# MCU.net
KiCad netlist of a schematic drawn in Altium Designer
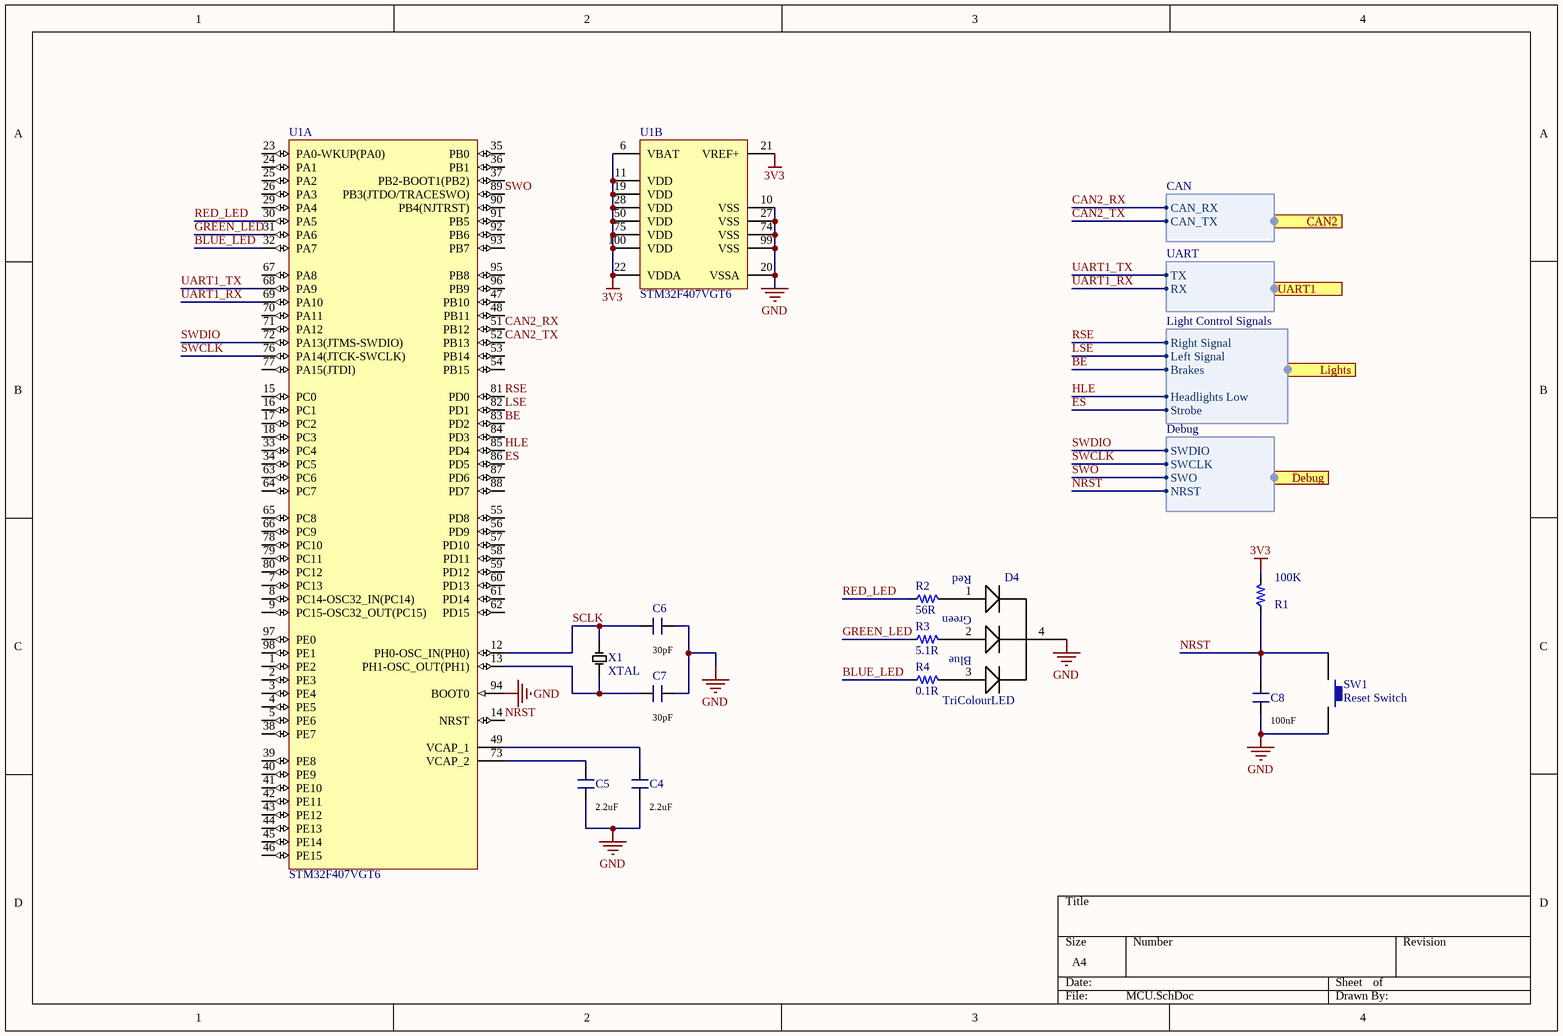
[diagram p0: MCU.SchDoc]

(export (version "E")
  (design (tool "Eeschema 10.0.6"))
  (components
    (comp (ref "C4")
      (value "SCH_GENERIC_CAPACITOR_0603")
      (footprint "PCB_GENERIC_SMD_0603")
      (description "Generic SMD capacitor 0603")
      (fields (field (name "TOLERANCE") "*%") (field (name "CAPACITANCE") "2.2uF"))
      (libsource (lib "Capacitors") (part "SCH_GENERIC_CAPACITOR_0603"))
    )
    (comp (ref "C5")
      (value "SCH_GENERIC_CAPACITOR_0603")
      (footprint "PCB_GENERIC_SMD_0603")
      (description "Generic SMD capacitor 0603")
      (fields (field (name "TOLERANCE") "*%") (field (name "CAPACITANCE") "2.2uF"))
      (libsource (lib "Capacitors") (part "SCH_GENERIC_CAPACITOR_0603"))
    )
    (comp (ref "C6")
      (value "SCH_GENERIC_CAPACITOR_0603")
      (footprint "PCB_GENERIC_SMD_0603")
      (description "Generic SMD capacitor 0603")
      (fields (field (name "TOLERANCE") "*%") (field (name "CAPACITANCE") "30pF"))
      (libsource (lib "Capacitors") (part "SCH_GENERIC_CAPACITOR_0603"))
    )
    (comp (ref "C7")
      (value "SCH_GENERIC_CAPACITOR_0603")
      (footprint "PCB_GENERIC_SMD_0603")
      (description "Generic SMD capacitor 0603")
      (fields (field (name "TOLERANCE") "*%") (field (name "CAPACITANCE") "30pF"))
      (libsource (lib "Capacitors") (part "SCH_GENERIC_CAPACITOR_0603"))
    )
    (comp (ref "C8")
      (value "SCH_GENERIC_CAPACITOR_0603")
      (footprint "PCB_GENERIC_SMD_0603")
      (description "Generic SMD capacitor 0603")
      (fields (field (name "TOLERANCE") "*%") (field (name "CAPACITANCE") "100nF"))
      (libsource (lib "Capacitors") (part "SCH_GENERIC_CAPACITOR_0603"))
    )
    (comp (ref "D4")
      (value "TriColourLED")
      (footprint "TricolourLED - SunLED - DK  1497-1225-2-ND")
      (libsource (lib "TricolourLED - SunLED - DK 1497-1225-2-ND") (part "TriColourLED"))
    )
    (comp (ref "R1")
      (value "SCH_GENERIC_RESISTOR_0603")
      (footprint "Generic 0603 Resistor:PCB_GENERIC_SMD_0603")
      (description "Generic SMD resistor 0603")
      (fields (field (name "RESISTANCE") "100K"))
      (libsource (lib "Resistors") (part "SCH_GENERIC_RESISTOR_0603"))
    )
    (comp (ref "R2")
      (value "SCH_GENERIC_RESISTOR_0603")
      (footprint "Generic 0603 Resistor:PCB_GENERIC_SMD_0603")
      (description "Generic SMD resistor 0603")
      (fields (field (name "RESISTANCE") "56R"))
      (libsource (lib "SCH_GENERIC_RESISTOR_0603") (part "SCH_GENERIC_RESISTOR_0603"))
    )
    (comp (ref "R3")
      (value "SCH_GENERIC_RESISTOR_0603")
      (footprint "Generic 0603 Resistor:PCB_GENERIC_SMD_0603")
      (description "Generic SMD resistor 0603")
      (fields (field (name "RESISTANCE") "5.1R"))
      (libsource (lib "SCH_GENERIC_RESISTOR_0603") (part "SCH_GENERIC_RESISTOR_0603"))
    )
    (comp (ref "R4")
      (value "SCH_GENERIC_RESISTOR_0603")
      (footprint "Generic 0603 Resistor:PCB_GENERIC_SMD_0603")
      (description "Generic SMD resistor 0603")
      (fields (field (name "RESISTANCE") "0.1R"))
      (libsource (lib "SCH_GENERIC_RESISTOR_0603") (part "SCH_GENERIC_RESISTOR_0603"))
    )
    (comp (ref "SW1")
      (value "Reset Switch")
      (footprint "Push Button Switch")
      (libsource (lib "PushButtonSwitch") (part "PushButtonSwitch"))
    )
    (comp (ref "U1")
      (value "STM32F407VGT6")
      (footprint "STM-LQFP100_N")
      (fields (field (name "MANUFACTURER") "STMicroelectronics"))
      (libsource (lib "STMicroelectronics STM32 F4") (part "STM32F407VGT6"))
    )
    (comp (ref "X1") (value "XTAL") (footprint "CRYSTAL_8MHZ") (libsource (lib "Crystal") (part "Crystal")))
  )
  (nets
    (net (code "7") (name "/BE") (class "Default")
      (node (ref "U1") (pin "83") (pinfunction "PD2_83") (pintype "bidirectional"))
    )
    (net (code "8") (name "/BLUE_LED") (class "Default")
      (node (ref "R4") (pin "1") (pinfunction "1_1") (pintype "passive"))
      (node (ref "U1") (pin "32") (pinfunction "PA7_32") (pintype "bidirectional"))
    )
    (net (code "9") (name "/CAN2_RX") (class "Default")
      (node (ref "U1") (pin "51") (pinfunction "PB12_51") (pintype "bidirectional"))
    )
    (net (code "10") (name "/CAN2_TX") (class "Default")
      (node (ref "U1") (pin "52") (pinfunction "PB13_52") (pintype "bidirectional"))
    )
    (net (code "11") (name "/ES") (class "Default")
      (node (ref "U1") (pin "86") (pinfunction "PD5_86") (pintype "bidirectional"))
    )
    (net (code "12") (name "/GREEN_LED") (class "Default")
      (node (ref "R3") (pin "1") (pinfunction "1_1") (pintype "passive"))
      (node (ref "U1") (pin "31") (pinfunction "PA6_31") (pintype "bidirectional"))
    )
    (net (code "13") (name "/HLE") (class "Default")
      (node (ref "U1") (pin "85") (pinfunction "PD4_85") (pintype "bidirectional"))
    )
    (net (code "14") (name "/LSE") (class "Default")
      (node (ref "U1") (pin "82") (pinfunction "PD1_82") (pintype "bidirectional"))
    )
    (net (code "15") (name "/NRST") (class "Default")
      (node (ref "C8") (pin "1") (pinfunction "1_1") (pintype "passive"))
      (node (ref "R1") (pin "1") (pinfunction "1_1") (pintype "passive"))
      (node (ref "SW1") (pin "1") (pinfunction "1_1") (pintype "passive"))
      (node (ref "U1") (pin "14") (pinfunction "NRST_14") (pintype "bidirectional"))
    )
    (net (code "16") (name "/RED_LED") (class "Default")
      (node (ref "R2") (pin "1") (pinfunction "1_1") (pintype "passive"))
      (node (ref "U1") (pin "30") (pinfunction "PA5_30") (pintype "bidirectional"))
    )
    (net (code "17") (name "/RSE") (class "Default")
      (node (ref "U1") (pin "81") (pinfunction "PD0_81") (pintype "bidirectional"))
    )
    (net (code "18") (name "/SCLK") (class "Default")
      (node (ref "C6") (pin "2") (pinfunction "2_2") (pintype "passive"))
      (node (ref "U1") (pin "12") (pinfunction "PH0-OSC_IN(PH0)_12") (pintype "bidirectional"))
      (node (ref "X1") (pin "1") (pintype "passive"))
    )
    (net (code "19") (name "/SWCLK") (class "Default")
      (node (ref "U1") (pin "76") (pinfunction "PA14(JTCK-SWCLK)_76") (pintype "bidirectional"))
    )
    (net (code "20") (name "/SWDIO") (class "Default")
      (node (ref "U1") (pin "72") (pinfunction "PA13(JTMS-SWDIO)_72") (pintype "bidirectional"))
    )
    (net (code "21") (name "/SWO") (class "Default")
      (node (ref "U1") (pin "89") (pinfunction "PB3(JTDO/TRACESWO)_89") (pintype "bidirectional"))
    )
    (net (code "22") (name "/UART1_RX") (class "Default")
      (node (ref "U1") (pin "69") (pinfunction "PA10_69") (pintype "bidirectional"))
    )
    (net (code "23") (name "/UART1_TX") (class "Default")
      (node (ref "U1") (pin "68") (pinfunction "PA9_68") (pintype "bidirectional"))
    )
    (net (code "28") (name "3V3") (class "Default")
      (node (ref "R1") (pin "2") (pinfunction "2_2") (pintype "passive"))
      (node (ref "U1") (pin "100") (pinfunction "VDD_100") (pintype "power_in"))
      (node (ref "U1") (pin "11") (pinfunction "VDD_11") (pintype "power_in"))
      (node (ref "U1") (pin "19") (pinfunction "VDD_19") (pintype "power_in"))
      (node (ref "U1") (pin "21") (pinfunction "VREF+_21") (pintype "power_in"))
      (node (ref "U1") (pin "22") (pinfunction "VDDA_22") (pintype "power_in"))
      (node (ref "U1") (pin "28") (pinfunction "VDD_28") (pintype "power_in"))
      (node (ref "U1") (pin "50") (pinfunction "VDD_50") (pintype "power_in"))
      (node (ref "U1") (pin "6") (pinfunction "VBAT_6") (pintype "power_in"))
      (node (ref "U1") (pin "75") (pinfunction "VDD_75") (pintype "power_in"))
    )
    (net (code "29") (name "GND") (class "Default")
      (node (ref "C4") (pin "1") (pinfunction "1_1") (pintype "passive"))
      (node (ref "C5") (pin "1") (pinfunction "1_1") (pintype "passive"))
      (node (ref "C6") (pin "1") (pinfunction "1_1") (pintype "passive"))
      (node (ref "C7") (pin "1") (pinfunction "1_1") (pintype "passive"))
      (node (ref "C8") (pin "2") (pinfunction "2_2") (pintype "passive"))
      (node (ref "D4") (pin "4") (pinfunction "4_4") (pintype "passive"))
      (node (ref "SW1") (pin "2") (pinfunction "2_2") (pintype "passive"))
      (node (ref "U1") (pin "10") (pinfunction "VSS_10") (pintype "power_in"))
      (node (ref "U1") (pin "20") (pinfunction "VSSA_20") (pintype "power_in"))
      (node (ref "U1") (pin "27") (pinfunction "VSS_27") (pintype "power_in"))
      (node (ref "U1") (pin "74") (pinfunction "VSS_74") (pintype "power_in"))
      (node (ref "U1") (pin "94") (pinfunction "BOOT0_94") (pintype "input"))
      (node (ref "U1") (pin "99") (pinfunction "VSS_99") (pintype "power_in"))
    )
    (net (code "30") (name "Net-(D4-Blue)") (class "Default")
      (node (ref "D4") (pin "3") (pinfunction "Blue_3") (pintype "passive"))
      (node (ref "R4") (pin "2") (pinfunction "2_2") (pintype "passive"))
    )
    (net (code "31") (name "Net-(D4-Green)") (class "Default")
      (node (ref "D4") (pin "2") (pinfunction "Green_2") (pintype "passive"))
      (node (ref "R3") (pin "2") (pinfunction "2_2") (pintype "passive"))
    )
    (net (code "32") (name "Net-(D4-Red)") (class "Default")
      (node (ref "D4") (pin "1") (pinfunction "Red_1") (pintype "passive"))
      (node (ref "R2") (pin "2") (pinfunction "2_2") (pintype "passive"))
    )
    (net (code "33") (name "Net-(U1A-PH1-OSC_OUT(PH1))") (class "Default")
      (node (ref "C7") (pin "2") (pinfunction "2_2") (pintype "passive"))
      (node (ref "U1") (pin "13") (pinfunction "PH1-OSC_OUT(PH1)_13") (pintype "bidirectional"))
      (node (ref "X1") (pin "2") (pintype "passive"))
    )
    (net (code "34") (name "Net-(U1A-VCAP_1)") (class "Default")
      (node (ref "C4") (pin "2") (pinfunction "2_2") (pintype "passive"))
      (node (ref "U1") (pin "49") (pinfunction "VCAP_1_49") (pintype "power_in"))
    )
    (net (code "35") (name "Net-(U1A-VCAP_2)") (class "Default")
      (node (ref "C5") (pin "2") (pinfunction "2_2") (pintype "passive"))
      (node (ref "U1") (pin "73") (pinfunction "VCAP_2_73") (pintype "power_in"))
    )
    (net (code "36") (name "unconnected-(U1A-PA0-WKUP(PA0)-Pad23)") (class "Default")
      (node (ref "U1") (pin "23") (pinfunction "PA0-WKUP(PA0)_23") (pintype "bidirectional"))
    )
    (net (code "37") (name "unconnected-(U1A-PA1-Pad24)") (class "Default")
      (node (ref "U1") (pin "24") (pinfunction "PA1_24") (pintype "bidirectional"))
    )
    (net (code "38") (name "unconnected-(U1A-PA2-Pad25)") (class "Default")
      (node (ref "U1") (pin "25") (pinfunction "PA2_25") (pintype "bidirectional"))
    )
    (net (code "39") (name "unconnected-(U1A-PA3-Pad26)") (class "Default")
      (node (ref "U1") (pin "26") (pinfunction "PA3_26") (pintype "bidirectional"))
    )
    (net (code "40") (name "unconnected-(U1A-PA4-Pad29)") (class "Default")
      (node (ref "U1") (pin "29") (pinfunction "PA4_29") (pintype "bidirectional"))
    )
    (net (code "41") (name "unconnected-(U1A-PA8-Pad67)") (class "Default")
      (node (ref "U1") (pin "67") (pinfunction "PA8_67") (pintype "bidirectional"))
    )
    (net (code "42") (name "unconnected-(U1A-PA11-Pad70)") (class "Default")
      (node (ref "U1") (pin "70") (pinfunction "PA11_70") (pintype "bidirectional"))
    )
    (net (code "43") (name "unconnected-(U1A-PA12-Pad71)") (class "Default")
      (node (ref "U1") (pin "71") (pinfunction "PA12_71") (pintype "bidirectional"))
    )
    (net (code "44") (name "unconnected-(U1A-PA15(JTDI)-Pad77)") (class "Default")
      (node (ref "U1") (pin "77") (pinfunction "PA15(JTDI)_77") (pintype "bidirectional"))
    )
    (net (code "45") (name "unconnected-(U1A-PB0-Pad35)") (class "Default")
      (node (ref "U1") (pin "35") (pinfunction "PB0_35") (pintype "bidirectional"))
    )
    (net (code "46") (name "unconnected-(U1A-PB1-Pad36)") (class "Default")
      (node (ref "U1") (pin "36") (pinfunction "PB1_36") (pintype "bidirectional"))
    )
    (net (code "47") (name "unconnected-(U1A-PB2-BOOT1(PB2)-Pad37)") (class "Default")
      (node (ref "U1") (pin "37") (pinfunction "PB2-BOOT1(PB2)_37") (pintype "bidirectional"))
    )
    (net (code "48") (name "unconnected-(U1A-PB4(NJTRST)-Pad90)") (class "Default")
      (node (ref "U1") (pin "90") (pinfunction "PB4(NJTRST)_90") (pintype "bidirectional"))
    )
    (net (code "49") (name "unconnected-(U1A-PB5-Pad91)") (class "Default")
      (node (ref "U1") (pin "91") (pinfunction "PB5_91") (pintype "bidirectional"))
    )
    (net (code "50") (name "unconnected-(U1A-PB6-Pad92)") (class "Default")
      (node (ref "U1") (pin "92") (pinfunction "PB6_92") (pintype "bidirectional"))
    )
    (net (code "51") (name "unconnected-(U1A-PB7-Pad93)") (class "Default")
      (node (ref "U1") (pin "93") (pinfunction "PB7_93") (pintype "bidirectional"))
    )
    (net (code "52") (name "unconnected-(U1A-PB8-Pad95)") (class "Default")
      (node (ref "U1") (pin "95") (pinfunction "PB8_95") (pintype "bidirectional"))
    )
    (net (code "53") (name "unconnected-(U1A-PB9-Pad96)") (class "Default")
      (node (ref "U1") (pin "96") (pinfunction "PB9_96") (pintype "bidirectional"))
    )
    (net (code "54") (name "unconnected-(U1A-PB10-Pad47)") (class "Default")
      (node (ref "U1") (pin "47") (pinfunction "PB10_47") (pintype "bidirectional"))
    )
    (net (code "55") (name "unconnected-(U1A-PB11-Pad48)") (class "Default")
      (node (ref "U1") (pin "48") (pinfunction "PB11_48") (pintype "bidirectional"))
    )
    (net (code "56") (name "unconnected-(U1A-PB14-Pad53)") (class "Default")
      (node (ref "U1") (pin "53") (pinfunction "PB14_53") (pintype "bidirectional"))
    )
    (net (code "57") (name "unconnected-(U1A-PB15-Pad54)") (class "Default")
      (node (ref "U1") (pin "54") (pinfunction "PB15_54") (pintype "bidirectional"))
    )
    (net (code "58") (name "unconnected-(U1A-PC0-Pad15)") (class "Default")
      (node (ref "U1") (pin "15") (pinfunction "PC0_15") (pintype "bidirectional"))
    )
    (net (code "59") (name "unconnected-(U1A-PC1-Pad16)") (class "Default")
      (node (ref "U1") (pin "16") (pinfunction "PC1_16") (pintype "bidirectional"))
    )
    (net (code "60") (name "unconnected-(U1A-PC2-Pad17)") (class "Default")
      (node (ref "U1") (pin "17") (pinfunction "PC2_17") (pintype "bidirectional"))
    )
    (net (code "61") (name "unconnected-(U1A-PC3-Pad18)") (class "Default")
      (node (ref "U1") (pin "18") (pinfunction "PC3_18") (pintype "bidirectional"))
    )
    (net (code "62") (name "unconnected-(U1A-PC4-Pad33)") (class "Default")
      (node (ref "U1") (pin "33") (pinfunction "PC4_33") (pintype "bidirectional"))
    )
    (net (code "63") (name "unconnected-(U1A-PC5-Pad34)") (class "Default")
      (node (ref "U1") (pin "34") (pinfunction "PC5_34") (pintype "bidirectional"))
    )
    (net (code "64") (name "unconnected-(U1A-PC6-Pad63)") (class "Default")
      (node (ref "U1") (pin "63") (pinfunction "PC6_63") (pintype "bidirectional"))
    )
    (net (code "65") (name "unconnected-(U1A-PC7-Pad64)") (class "Default")
      (node (ref "U1") (pin "64") (pinfunction "PC7_64") (pintype "bidirectional"))
    )
    (net (code "66") (name "unconnected-(U1A-PC8-Pad65)") (class "Default")
      (node (ref "U1") (pin "65") (pinfunction "PC8_65") (pintype "bidirectional"))
    )
    (net (code "67") (name "unconnected-(U1A-PC9-Pad66)") (class "Default")
      (node (ref "U1") (pin "66") (pinfunction "PC9_66") (pintype "bidirectional"))
    )
    (net (code "68") (name "unconnected-(U1A-PC10-Pad78)") (class "Default")
      (node (ref "U1") (pin "78") (pinfunction "PC10_78") (pintype "bidirectional"))
    )
    (net (code "69") (name "unconnected-(U1A-PC11-Pad79)") (class "Default")
      (node (ref "U1") (pin "79") (pinfunction "PC11_79") (pintype "bidirectional"))
    )
    (net (code "70") (name "unconnected-(U1A-PC12-Pad80)") (class "Default")
      (node (ref "U1") (pin "80") (pinfunction "PC12_80") (pintype "bidirectional"))
    )
    (net (code "71") (name "unconnected-(U1A-PC13-Pad7)") (class "Default")
      (node (ref "U1") (pin "7") (pinfunction "PC13_7") (pintype "bidirectional"))
    )
    (net (code "72") (name "unconnected-(U1A-PC14-OSC32_IN(PC14)-Pad8)") (class "Default")
      (node (ref "U1") (pin "8") (pinfunction "PC14-OSC32_IN(PC14)_8") (pintype "bidirectional"))
    )
    (net (code "73") (name "unconnected-(U1A-PC15-OSC32_OUT(PC15)-Pad9)") (class "Default")
      (node (ref "U1") (pin "9") (pinfunction "PC15-OSC32_OUT(PC15)_9") (pintype "bidirectional"))
    )
    (net (code "74") (name "unconnected-(U1A-PD3-Pad84)") (class "Default")
      (node (ref "U1") (pin "84") (pinfunction "PD3_84") (pintype "bidirectional"))
    )
    (net (code "75") (name "unconnected-(U1A-PD6-Pad87)") (class "Default")
      (node (ref "U1") (pin "87") (pinfunction "PD6_87") (pintype "bidirectional"))
    )
    (net (code "76") (name "unconnected-(U1A-PD7-Pad88)") (class "Default")
      (node (ref "U1") (pin "88") (pinfunction "PD7_88") (pintype "bidirectional"))
    )
    (net (code "77") (name "unconnected-(U1A-PD8-Pad55)") (class "Default")
      (node (ref "U1") (pin "55") (pinfunction "PD8_55") (pintype "bidirectional"))
    )
    (net (code "78") (name "unconnected-(U1A-PD9-Pad56)") (class "Default")
      (node (ref "U1") (pin "56") (pinfunction "PD9_56") (pintype "bidirectional"))
    )
    (net (code "79") (name "unconnected-(U1A-PD10-Pad57)") (class "Default")
      (node (ref "U1") (pin "57") (pinfunction "PD10_57") (pintype "bidirectional"))
    )
    (net (code "80") (name "unconnected-(U1A-PD11-Pad58)") (class "Default")
      (node (ref "U1") (pin "58") (pinfunction "PD11_58") (pintype "bidirectional"))
    )
    (net (code "81") (name "unconnected-(U1A-PD12-Pad59)") (class "Default")
      (node (ref "U1") (pin "59") (pinfunction "PD12_59") (pintype "bidirectional"))
    )
    (net (code "82") (name "unconnected-(U1A-PD13-Pad60)") (class "Default")
      (node (ref "U1") (pin "60") (pinfunction "PD13_60") (pintype "bidirectional"))
    )
    (net (code "83") (name "unconnected-(U1A-PD14-Pad61)") (class "Default")
      (node (ref "U1") (pin "61") (pinfunction "PD14_61") (pintype "bidirectional"))
    )
    (net (code "84") (name "unconnected-(U1A-PD15-Pad62)") (class "Default")
      (node (ref "U1") (pin "62") (pinfunction "PD15_62") (pintype "bidirectional"))
    )
    (net (code "85") (name "unconnected-(U1A-PE0-Pad97)") (class "Default")
      (node (ref "U1") (pin "97") (pinfunction "PE0_97") (pintype "bidirectional"))
    )
    (net (code "86") (name "unconnected-(U1A-PE1-Pad98)") (class "Default")
      (node (ref "U1") (pin "98") (pinfunction "PE1_98") (pintype "bidirectional"))
    )
    (net (code "87") (name "unconnected-(U1A-PE2-Pad1)") (class "Default")
      (node (ref "U1") (pin "1") (pinfunction "PE2_1") (pintype "bidirectional"))
    )
    (net (code "88") (name "unconnected-(U1A-PE3-Pad2)") (class "Default")
      (node (ref "U1") (pin "2") (pinfunction "PE3_2") (pintype "bidirectional"))
    )
    (net (code "89") (name "unconnected-(U1A-PE4-Pad3)") (class "Default")
      (node (ref "U1") (pin "3") (pinfunction "PE4_3") (pintype "bidirectional"))
    )
    (net (code "90") (name "unconnected-(U1A-PE5-Pad4)") (class "Default")
      (node (ref "U1") (pin "4") (pinfunction "PE5_4") (pintype "bidirectional"))
    )
    (net (code "91") (name "unconnected-(U1A-PE6-Pad5)") (class "Default")
      (node (ref "U1") (pin "5") (pinfunction "PE6_5") (pintype "bidirectional"))
    )
    (net (code "92") (name "unconnected-(U1A-PE7-Pad38)") (class "Default")
      (node (ref "U1") (pin "38") (pinfunction "PE7_38") (pintype "bidirectional"))
    )
    (net (code "93") (name "unconnected-(U1A-PE8-Pad39)") (class "Default")
      (node (ref "U1") (pin "39") (pinfunction "PE8_39") (pintype "bidirectional"))
    )
    (net (code "94") (name "unconnected-(U1A-PE9-Pad40)") (class "Default")
      (node (ref "U1") (pin "40") (pinfunction "PE9_40") (pintype "bidirectional"))
    )
    (net (code "95") (name "unconnected-(U1A-PE10-Pad41)") (class "Default")
      (node (ref "U1") (pin "41") (pinfunction "PE10_41") (pintype "bidirectional"))
    )
    (net (code "96") (name "unconnected-(U1A-PE11-Pad42)") (class "Default")
      (node (ref "U1") (pin "42") (pinfunction "PE11_42") (pintype "bidirectional"))
    )
    (net (code "97") (name "unconnected-(U1A-PE12-Pad43)") (class "Default")
      (node (ref "U1") (pin "43") (pinfunction "PE12_43") (pintype "bidirectional"))
    )
    (net (code "98") (name "unconnected-(U1A-PE13-Pad44)") (class "Default")
      (node (ref "U1") (pin "44") (pinfunction "PE13_44") (pintype "bidirectional"))
    )
    (net (code "99") (name "unconnected-(U1A-PE14-Pad45)") (class "Default")
      (node (ref "U1") (pin "45") (pinfunction "PE14_45") (pintype "bidirectional"))
    )
    (net (code "100") (name "unconnected-(U1A-PE15-Pad46)") (class "Default")
      (node (ref "U1") (pin "46") (pinfunction "PE15_46") (pintype "bidirectional"))
    )
  )
)
